# pga460_direct.net
KiCad netlist of a schematic drawn in EAGLE
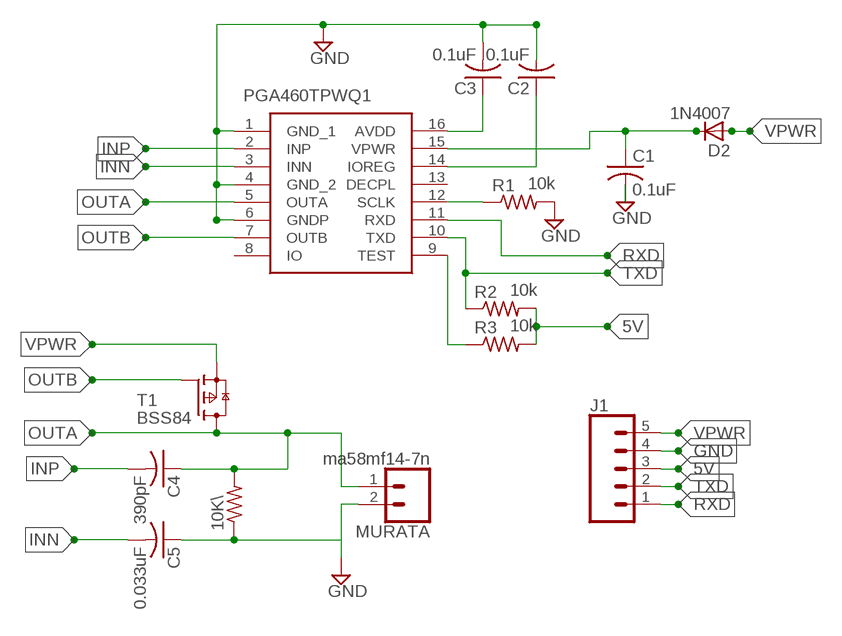
[diagram p0: schematic, sheet 1]

(export (version "E")
  (design (tool "Eeschema 10.0.6"))
  (components
    (comp (ref "10K\\")
      (value "R-US_M0805")
      (footprint "eagle-import:M0805")
      (libsource (lib "eagle-import") (part "R-US_M0805"))
    )
    (comp (ref "C1")
      (value "0.1uF")
      (footprint "eagle-import:C0805")
      (libsource (lib "eagle-import") (part "C-USC0805"))
    )
    (comp (ref "C2")
      (value "0.1uF")
      (footprint "eagle-import:C0805")
      (libsource (lib "eagle-import") (part "C-USC0805"))
    )
    (comp (ref "C3")
      (value "0.1uF")
      (footprint "eagle-import:C0805")
      (libsource (lib "eagle-import") (part "C-USC0805"))
    )
    (comp (ref "C4")
      (value "390pF")
      (footprint "eagle-import:C0805")
      (libsource (lib "eagle-import") (part "C-USC0805"))
    )
    (comp (ref "C5")
      (value "0.033uF")
      (footprint "eagle-import:C0805")
      (libsource (lib "eagle-import") (part "C-USC0805"))
    )
    (comp (ref "D2")
      (value "1N4007")
      (footprint "eagle-import:SMA")
      (libsource (lib "eagle-import") (part "1N4007"))
    )
    (comp (ref "IC1")
      (value "PGA460TPWQ1")
      (footprint "eagle-import:SOP65P640X120-16N")
      (fields (field (name "MOUSER_PART_NUMBER") "595-PGA460TPWQ1"))
      (libsource (lib "eagle-import") (part "PGA460TPWQ1"))
    )
    (comp (ref "J1")
      (value "CONN_05")
      (footprint "eagle-import:1X05")
      (libsource (lib "eagle-import") (part "CONN_05"))
    )
    (comp (ref "MURATA")
      (value "ma58mf14-7n")
      (footprint "eagle-import:1X02_LOCK")
      (libsource (lib "eagle-import") (part "CONN_02LOCK"))
    )
    (comp (ref "R1")
      (value "10k")
      (footprint "eagle-import:R0805")
      (libsource (lib "eagle-import") (part "R-US_R0805"))
    )
    (comp (ref "R2")
      (value "10k")
      (footprint "eagle-import:R0805")
      (libsource (lib "eagle-import") (part "R-US_R0805"))
    )
    (comp (ref "R3")
      (value "10k")
      (footprint "eagle-import:R0805")
      (libsource (lib "eagle-import") (part "R-US_R0805"))
    )
    (comp (ref "T1")
      (value "BSS84")
      (footprint "eagle-import:SOT23")
      (libsource (lib "eagle-import") (part "BSS84"))
    )
  )
  (nets
    (net (code "1") (name "5V") (class "Default")
      (node (ref "J1") (pin "3") (pinfunction "3_3") (pintype "passive"))
      (node (ref "R2") (pin "2") (pinfunction "2_2") (pintype "passive"))
      (node (ref "R3") (pin "2") (pinfunction "2_2") (pintype "passive"))
    )
    (net (code "2") (name "GND") (class "Default")
      (node (ref "10K\\") (pin "1") (pinfunction "1_1") (pintype "passive"))
      (node (ref "C1") (pin "2") (pinfunction "2_2") (pintype "passive"))
      (node (ref "C2") (pin "2") (pinfunction "2_2") (pintype "passive"))
      (node (ref "C3") (pin "2") (pinfunction "2_2") (pintype "passive"))
      (node (ref "C5") (pin "1") (pinfunction "1_1") (pintype "passive"))
      (node (ref "IC1") (pin "1") (pinfunction "GND_1_1") (pintype "power_in"))
      (node (ref "IC1") (pin "4") (pinfunction "GND_2_4") (pintype "power_in"))
      (node (ref "IC1") (pin "6") (pinfunction "GNDP_6") (pintype "power_in"))
      (node (ref "J1") (pin "4") (pinfunction "4_4") (pintype "passive"))
      (node (ref "MURATA") (pin "2") (pinfunction "2_2") (pintype "passive"))
      (node (ref "R1") (pin "2") (pinfunction "2_2") (pintype "passive"))
    )
    (net (code "3") (name "INN") (class "Default")
      (node (ref "C5") (pin "2") (pinfunction "2_2") (pintype "passive"))
      (node (ref "IC1") (pin "3") (pinfunction "INN_3") (pintype "input"))
    )
    (net (code "4") (name "INP") (class "Default")
      (node (ref "C4") (pin "2") (pinfunction "2_2") (pintype "passive"))
      (node (ref "IC1") (pin "2") (pinfunction "INP_2") (pintype "input"))
    )
    (net (code "5") (name "Net-(D2-C)") (class "Default")
      (node (ref "C1") (pin "1") (pinfunction "1_1") (pintype "passive"))
      (node (ref "D2") (pin "K") (pinfunction "C_K") (pintype "passive"))
      (node (ref "IC1") (pin "15") (pinfunction "VPWR_15") (pintype "power_in"))
    )
    (net (code "6") (name "Net-(IC1-AVDD)") (class "Default")
      (node (ref "C3") (pin "1") (pinfunction "1_1") (pintype "passive"))
      (node (ref "IC1") (pin "16") (pinfunction "AVDD_16") (pintype "power_in"))
    )
    (net (code "7") (name "Net-(IC1-IOREG)") (class "Default")
      (node (ref "C2") (pin "1") (pinfunction "1_1") (pintype "passive"))
      (node (ref "IC1") (pin "14") (pinfunction "IOREG_14") (pintype "power_in"))
    )
    (net (code "8") (name "Net-(IC1-SCLK)") (class "Default")
      (node (ref "IC1") (pin "12") (pinfunction "SCLK_12") (pintype "input"))
      (node (ref "R1") (pin "1") (pinfunction "1_1") (pintype "passive"))
    )
    (net (code "9") (name "Net-(IC1-TEST)") (class "Default")
      (node (ref "IC1") (pin "9") (pinfunction "TEST_9") (pintype "bidirectional"))
      (node (ref "R3") (pin "1") (pinfunction "1_1") (pintype "passive"))
    )
    (net (code "10") (name "OUTA") (class "Default")
      (node (ref "10K\\") (pin "2") (pinfunction "2_2") (pintype "passive"))
      (node (ref "C4") (pin "1") (pinfunction "1_1") (pintype "passive"))
      (node (ref "IC1") (pin "5") (pinfunction "OUTA_5") (pintype "output"))
      (node (ref "MURATA") (pin "1") (pinfunction "1_1") (pintype "passive"))
      (node (ref "T1") (pin "3") (pinfunction "D_3") (pintype "passive"))
    )
    (net (code "11") (name "OUTB") (class "Default")
      (node (ref "IC1") (pin "7") (pinfunction "OUTB_7") (pintype "output"))
      (node (ref "T1") (pin "1") (pinfunction "G_1") (pintype "passive"))
    )
    (net (code "12") (name "RXD") (class "Default")
      (node (ref "IC1") (pin "11") (pinfunction "RXD_11") (pintype "input"))
      (node (ref "J1") (pin "1") (pinfunction "1_1") (pintype "passive"))
    )
    (net (code "13") (name "TXD") (class "Default")
      (node (ref "IC1") (pin "10") (pinfunction "TXD_10") (pintype "output"))
      (node (ref "J1") (pin "2") (pinfunction "2_2") (pintype "passive"))
      (node (ref "R2") (pin "1") (pinfunction "1_1") (pintype "passive"))
    )
    (net (code "14") (name "VPWR") (class "Default")
      (node (ref "D2") (pin "A") (pinfunction "A_A") (pintype "passive"))
      (node (ref "J1") (pin "5") (pinfunction "5_5") (pintype "passive"))
      (node (ref "T1") (pin "2") (pinfunction "S_2") (pintype "passive"))
    )
    (net (code "15") (name "unconnected-(IC1-DECPL-Pad13)") (class "Default")
      (node (ref "IC1") (pin "13") (pinfunction "DECPL_13") (pintype "output"))
    )
    (net (code "16") (name "unconnected-(IC1-IO-Pad8)") (class "Default")
      (node (ref "IC1") (pin "8") (pinfunction "IO_8") (pintype "bidirectional"))
    )
  )
)
